# ST-Link_Stlink_v2_02.net
KiCad netlist of a schematic drawn in Altium Designer
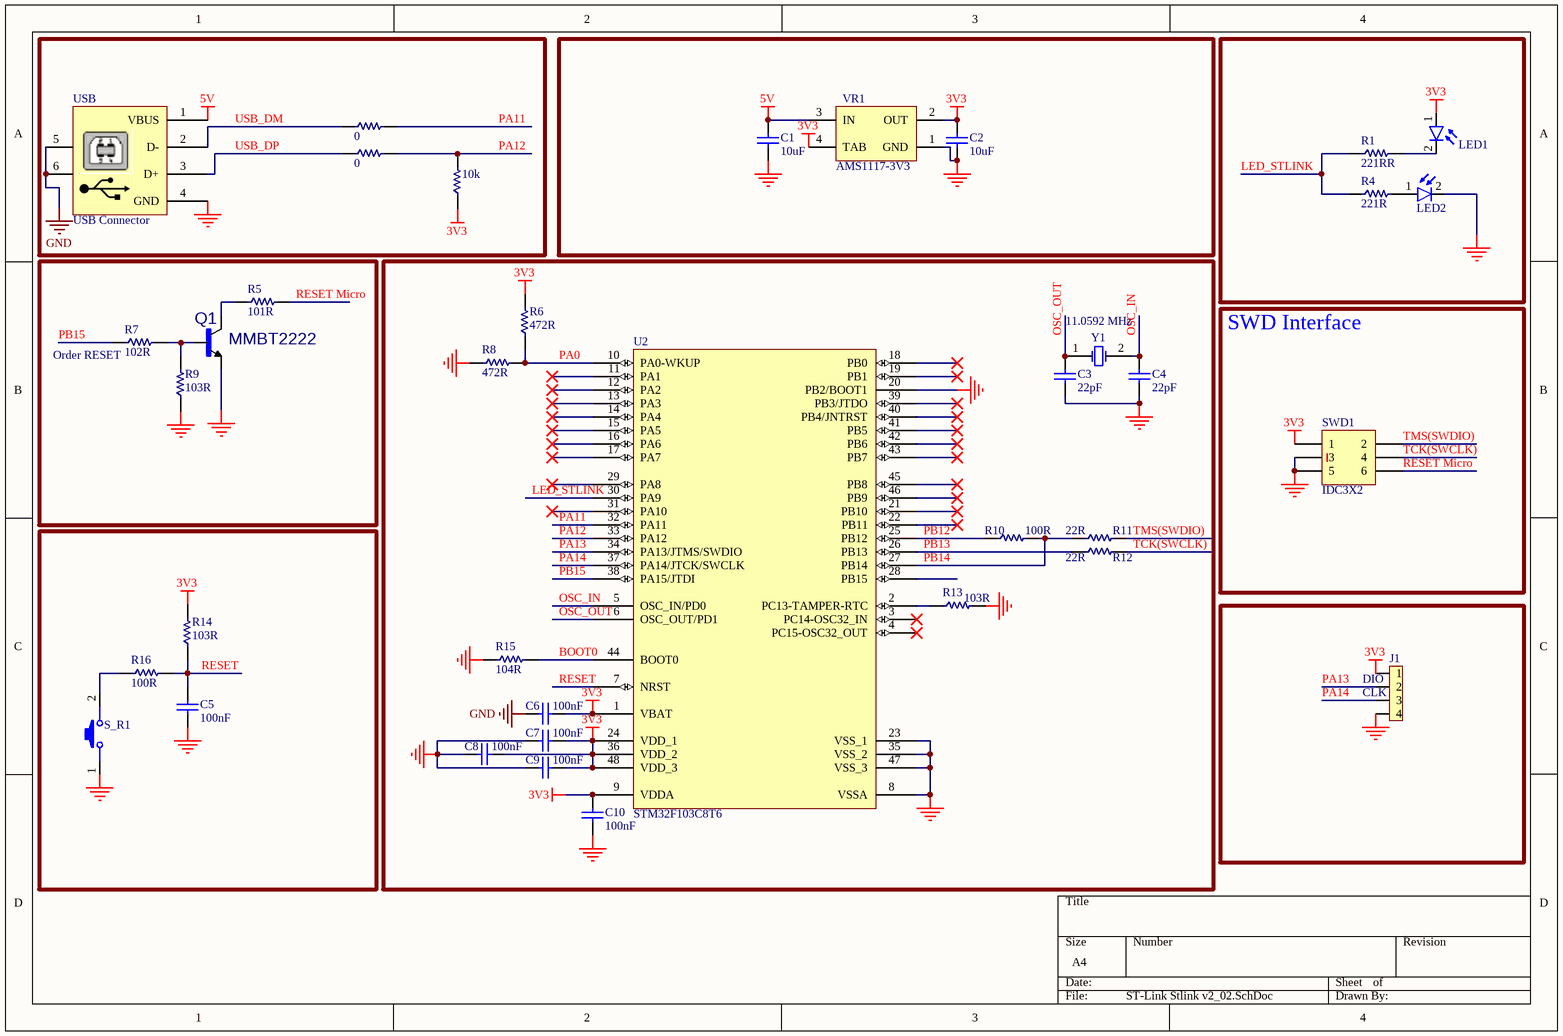
[diagram p0: ST-Link Stlink v2_02.SchDoc]

(export (version "E")
  (design (tool "Eeschema 10.0.6"))
  (components
    (comp (ref "C1")
      (value "10uF")
      (footprint "CAPC4817X12N")
      (description "CAP 1206")
      (fields (field (name "DESIGNER") "Abbas Basereh"))
      (libsource (lib "Panel Tester") (part "CAP SMD 1206"))
    )
    (comp (ref "C2")
      (value "10uF")
      (footprint "CAPC4817X12N")
      (description "CAP 1206")
      (fields (field (name "DESIGNER") "Abbas Basereh"))
      (libsource (lib "Panel Tester") (part "CAP SMD 1206"))
    )
    (comp (ref "C3")
      (value "22pF")
      (footprint "CAPC4817X12N")
      (description "CAP 1206")
      (fields (field (name "DESIGNER") "Abbas Basereh"))
      (libsource (lib "Panel Tester") (part "CAP SMD 1206"))
    )
    (comp (ref "C4")
      (value "22pF")
      (footprint "CAPC4817X12N")
      (description "CAP 1206")
      (fields (field (name "DESIGNER") "Abbas Basereh"))
      (libsource (lib "Panel Tester") (part "CAP SMD 1206"))
    )
    (comp (ref "C5")
      (value "100nF")
      (footprint "CAPC4817X12N")
      (description "CAP 1206")
      (fields (field (name "DESIGNER") "Abbas Basereh"))
      (libsource (lib "Panel Tester") (part "CAP SMD 1206"))
    )
    (comp (ref "C6")
      (value "100nF")
      (footprint "CAPC4817X12N")
      (description "CAP 1206")
      (fields (field (name "DESIGNER") "Abbas Basereh"))
      (libsource (lib "Panel Tester") (part "CAP SMD 1206"))
    )
    (comp (ref "C7")
      (value "100nF")
      (footprint "CAPC4817X12N")
      (description "CAP 1206")
      (fields (field (name "DESIGNER") "Abbas Basereh"))
      (libsource (lib "Panel Tester") (part "CAP SMD 1206"))
    )
    (comp (ref "C8")
      (value "100nF")
      (footprint "CAPC4817X12N")
      (description "CAP 1206")
      (fields (field (name "DESIGNER") "Abbas Basereh"))
      (libsource (lib "Panel Tester") (part "CAP SMD 1206"))
    )
    (comp (ref "C9")
      (value "100nF")
      (footprint "CAPC4817X12N")
      (description "CAP 1206")
      (fields (field (name "DESIGNER") "Abbas Basereh"))
      (libsource (lib "Panel Tester") (part "CAP SMD 1206"))
    )
    (comp (ref "C10")
      (value "100nF")
      (footprint "CAPC4817X12N")
      (description "CAP 1206")
      (fields (field (name "DESIGNER") "Abbas Basereh"))
      (libsource (lib "Panel Tester") (part "CAP SMD 1206"))
    )
    (comp (ref "J1")
      (value "Program Chip")
      (footprint "ZSIP04")
      (description "Connector")
      (libsource (lib "ZAltium2020SCH") (part "ZCON4"))
    )
    (comp (ref "LED1")
      (value "Color")
      (footprint "LED SMD 1206")
      (description "Infra Red Reciever Photo Diode")
      (fields (field (name "DESIGNER") "Saeid Jorablo"))
      (libsource (lib "NKH7000_Library") (part "LED"))
    )
    (comp (ref "LED2")
      (value "Color")
      (footprint "LED SMD 1206")
      (description "Infra Red Reciever Photo Diode")
      (fields (field (name "DESIGNER") "Saeid Jorablo"))
      (libsource (lib "NKH7000_Library") (part "LED"))
    )
    (comp (ref "Q1") (value "MMBT2222") (footprint "SOT23_BEC_M") (libsource (lib "OBD2") (part "MMBT2222")))
    (comp (ref "R1") (value "221RR") (footprint "RES1206") (libsource (lib "Panel Tester") (part "res")))
    (comp (ref "R2")
      (value "10k")
      (footprint "RES1206")
      (description "smd-1206-1%")
      (fields (field (name "PART") "resistor-smd-1206-10k") (field (name "DESIGNER") "rashid_behdarvand"))
      (libsource (lib "R_C_D_T") (part "resistor"))
    )
    (comp (ref "R4") (value "221R") (footprint "RES1206") (libsource (lib "Panel Tester") (part "res")))
    (comp (ref "R5") (value "101R") (footprint "RES1206") (libsource (lib "Panel Tester") (part "res")))
    (comp (ref "R6") (value "472R") (footprint "RES1206") (libsource (lib "Panel Tester") (part "res")))
    (comp (ref "R7") (value "102R") (footprint "RES1206") (libsource (lib "Panel Tester") (part "res")))
    (comp (ref "R8") (value "472R") (footprint "RES1206") (libsource (lib "Panel Tester") (part "res")))
    (comp (ref "R9") (value "103R") (footprint "RES1206") (libsource (lib "Panel Tester") (part "res")))
    (comp (ref "R10") (value "100R") (footprint "RES1206") (libsource (lib "Panel Tester") (part "res")))
    (comp (ref "R11") (value "22R") (footprint "RES1206") (libsource (lib "Panel Tester") (part "res")))
    (comp (ref "R12") (value "22R") (footprint "RES1206") (libsource (lib "Panel Tester") (part "res")))
    (comp (ref "R13") (value "103R") (footprint "RES1206") (libsource (lib "Panel Tester") (part "res")))
    (comp (ref "R14") (value "103R") (footprint "RES1206") (libsource (lib "Panel Tester") (part "res")))
    (comp (ref "R15") (value "104R") (footprint "RES1206") (libsource (lib "Panel Tester") (part "res")))
    (comp (ref "R16") (value "100R") (footprint "RES1206") (libsource (lib "Panel Tester") (part "res")))
    (comp (ref "R20")
      (value "0")
      (footprint "RES1206")
      (fields (field (name "PART") "resistor-smd-1206-0-ohm") (field (name "DESIGNER") "rashid_behdarvand"))
      (libsource (lib "R_C_D_T") (part "resistor"))
    )
    (comp (ref "R21")
      (value "0")
      (footprint "RES1206")
      (fields (field (name "PART") "resistor-smd-1206-0-ohm") (field (name "DESIGNER") "rashid_behdarvand"))
      (libsource (lib "R_C_D_T") (part "resistor"))
    )
    (comp (ref "SWD1")
      (value "IDC3X2")
      (footprint "IDC_2X3")
      (description "IDC, 6-Pin, Dual row")
      (fields (field (name "PUBLISHER") "Altium Limited"))
      (libsource (lib "Panel Tester") (part "IDC 3X2"))
    )
    (comp (ref "S_R1")
      (value "SW4")
      (footprint "SMD_ALPS_NEW")
      (description "2 Pin Push Button Switch")
      (fields (field (name "DESIGNER") "Eng. Saeid Jorablo"))
      (libsource (lib "Sensor_Simulation_Ver 03") (part "SW_PB2"))
    )
    (comp (ref "U2")
      (value "STM32F103C8T6")
      (footprint "LQFP48_M")
      (description "STM32 ARM-based 32-bit MCU with 64 Kbytes Flash, 48-pin LQFP, Industrial Temperature")
      (fields (field (name "PUBLISHER") "Altium Limited"))
      (libsource (lib "ST Microcontroller 32-Bit STM32") (part "STM32F103C8T6"))
    )
    (comp (ref "USB")
      (value "USB Connector")
      (footprint "USB2.5-2H4F")
      (description "USB Connector-B Type")
      (fields (field (name "DESIGNER") "Eng. Saeid Jorablo"))
      (libsource (lib "My Library") (part "USB"))
    )
    (comp (ref "VR1")
      (value "AMS1117-3V3")
      (footprint "MP04A_N")
      (description "x.x Volt, 800mA Low-Dropout Linear Regulator, 4-pin SOT-223")
      (fields
        (field (name "PARTNUMBER") "LM1117IMP-3.3")
        (field (name "MANUFACTURER") "National Semiconductor")
        (field (name "PUBLISHER") "Altium Limited")
      )
      (libsource (lib "My Library") (part "LM1117IMP-x.x"))
    )
    (comp (ref "Y1")
      (value "11.0592 MHz")
      (footprint "Crystal SMD")
      (description "XTAL Crystal")
      (libsource (lib "NKH7000_Library") (part "XTAL"))
    )
  )
  (nets
    (net (code "1") (name "/BOOT0") (class "Default")
      (node (ref "R15") (pin "2") (pinfunction "2_2") (pintype "passive"))
      (node (ref "U2") (pin "44") (pinfunction "BOOT0_44") (pintype "passive"))
    )
    (net (code "2") (name "/LED_STLINK") (class "Default")
      (node (ref "R1") (pin "1") (pinfunction "1_1") (pintype "passive"))
      (node (ref "R4") (pin "1") (pinfunction "1_1") (pintype "passive"))
      (node (ref "U2") (pin "30") (pinfunction "PA9_30") (pintype "bidirectional"))
    )
    (net (code "3") (name "/OSC_IN") (class "Default")
      (node (ref "C4") (pin "2") (pinfunction "2_2") (pintype "passive"))
      (node (ref "U2") (pin "5") (pinfunction "OSC_IN/PD0_5") (pintype "passive"))
      (node (ref "Y1") (pin "2") (pinfunction "OSC2_2") (pintype "passive"))
    )
    (net (code "4") (name "/OSC_OUT") (class "Default")
      (node (ref "C3") (pin "2") (pinfunction "2_2") (pintype "passive"))
      (node (ref "U2") (pin "6") (pinfunction "OSC_OUT/PD1_6") (pintype "passive"))
      (node (ref "Y1") (pin "1") (pinfunction "OSC1_1") (pintype "passive"))
    )
    (net (code "5") (name "/PA0") (class "Default")
      (node (ref "R6") (pin "1") (pinfunction "1_1") (pintype "passive"))
      (node (ref "R8") (pin "2") (pinfunction "2_2") (pintype "passive"))
      (node (ref "U2") (pin "10") (pinfunction "PA0-WKUP_10") (pintype "bidirectional"))
    )
    (net (code "6") (name "/PA11") (class "Default")
      (node (ref "R20") (pin "2") (pinfunction "2_2") (pintype "passive"))
      (node (ref "U2") (pin "32") (pinfunction "PA11_32") (pintype "bidirectional"))
    )
    (net (code "7") (name "/PA12") (class "Default")
      (node (ref "R2") (pin "2") (pinfunction "2_2") (pintype "passive"))
      (node (ref "R21") (pin "2") (pinfunction "2_2") (pintype "passive"))
      (node (ref "U2") (pin "33") (pinfunction "PA12_33") (pintype "bidirectional"))
    )
    (net (code "8") (name "/PA13") (class "Default")
      (node (ref "J1") (pin "2") (pinfunction "2_2") (pintype "passive"))
      (node (ref "U2") (pin "34") (pinfunction "PA13/JTMS/SWDIO_34") (pintype "bidirectional"))
    )
    (net (code "9") (name "/PA14") (class "Default")
      (node (ref "J1") (pin "3") (pinfunction "3_3") (pintype "passive"))
      (node (ref "U2") (pin "37") (pinfunction "PA14/JTCK/SWCLK_37") (pintype "bidirectional"))
    )
    (net (code "10") (name "/PB12") (class "Default")
      (node (ref "R10") (pin "1") (pinfunction "1_1") (pintype "passive"))
      (node (ref "U2") (pin "25") (pinfunction "PB12_25") (pintype "bidirectional"))
    )
    (net (code "11") (name "/PB13") (class "Default")
      (node (ref "R12") (pin "1") (pinfunction "1_1") (pintype "passive"))
      (node (ref "U2") (pin "26") (pinfunction "PB13_26") (pintype "bidirectional"))
    )
    (net (code "12") (name "/PB14") (class "Default")
      (node (ref "R10") (pin "2") (pinfunction "2_2") (pintype "passive"))
      (node (ref "R11") (pin "1") (pinfunction "1_1") (pintype "passive"))
      (node (ref "U2") (pin "27") (pinfunction "PB14_27") (pintype "bidirectional"))
    )
    (net (code "13") (name "/PB15") (class "Default")
      (node (ref "R7") (pin "1") (pinfunction "1_1") (pintype "passive"))
      (node (ref "U2") (pin "38") (pinfunction "PA15/JTDI_38") (pintype "bidirectional"))
    )
    (net (code "14") (name "/RESET") (class "Default")
      (node (ref "C5") (pin "2") (pinfunction "2_2") (pintype "passive"))
      (node (ref "R14") (pin "1") (pinfunction "1_1") (pintype "passive"))
      (node (ref "R16") (pin "2") (pinfunction "2_2") (pintype "passive"))
      (node (ref "U2") (pin "7") (pinfunction "NRST_7") (pintype "bidirectional"))
    )
    (net (code "15") (name "/RESET Micro") (class "Default")
      (node (ref "R5") (pin "2") (pinfunction "2_2") (pintype "passive"))
      (node (ref "SWD1") (pin "6") (pinfunction "6_6") (pintype "passive"))
    )
    (net (code "16") (name "/TCK(SWCLK)") (class "Default")
      (node (ref "R12") (pin "2") (pinfunction "2_2") (pintype "passive"))
      (node (ref "SWD1") (pin "4") (pinfunction "4_4") (pintype "passive"))
    )
    (net (code "17") (name "/TMS(SWDIO)") (class "Default")
      (node (ref "R11") (pin "2") (pinfunction "2_2") (pintype "passive"))
      (node (ref "SWD1") (pin "2") (pinfunction "2_2") (pintype "passive"))
    )
    (net (code "18") (name "/USB_DM") (class "Default")
      (node (ref "R20") (pin "1") (pinfunction "1_1") (pintype "passive"))
      (node (ref "USB") (pin "2") (pinfunction "D-_2") (pintype "passive"))
    )
    (net (code "19") (name "/USB_DP") (class "Default")
      (node (ref "R21") (pin "1") (pinfunction "1_1") (pintype "passive"))
      (node (ref "USB") (pin "3") (pinfunction "D+_3") (pintype "passive"))
    )
    (net (code "20") (name "3V3") (class "Default")
      (node (ref "C10") (pin "2") (pinfunction "2_2") (pintype "passive"))
      (node (ref "C2") (pin "2") (pinfunction "2_2") (pintype "passive"))
      (node (ref "C6") (pin "1") (pinfunction "1_1") (pintype "passive"))
      (node (ref "C7") (pin "1") (pinfunction "1_1") (pintype "passive"))
      (node (ref "C8") (pin "1") (pinfunction "1_1") (pintype "passive"))
      (node (ref "C9") (pin "1") (pinfunction "1_1") (pintype "passive"))
      (node (ref "J1") (pin "1") (pinfunction "1_1") (pintype "passive"))
      (node (ref "LED1") (pin "1") (pinfunction "A_1") (pintype "passive"))
      (node (ref "R14") (pin "2") (pinfunction "2_2") (pintype "passive"))
      (node (ref "R2") (pin "1") (pinfunction "1_1") (pintype "passive"))
      (node (ref "R6") (pin "2") (pinfunction "2_2") (pintype "passive"))
      (node (ref "SWD1") (pin "1") (pinfunction "1_1") (pintype "passive"))
      (node (ref "U2") (pin "1") (pinfunction "VBAT_1") (pintype "power_in"))
      (node (ref "U2") (pin "24") (pinfunction "VDD_1_24") (pintype "power_in"))
      (node (ref "U2") (pin "36") (pinfunction "VDD_2_36") (pintype "power_in"))
      (node (ref "U2") (pin "48") (pinfunction "VDD_3_48") (pintype "power_in"))
      (node (ref "U2") (pin "9") (pinfunction "VDDA_9") (pintype "power_in"))
      (node (ref "VR1") (pin "2") (pinfunction "OUT_2") (pintype "power_in"))
      (node (ref "VR1") (pin "4") (pinfunction "TAB_4") (pintype "power_in"))
    )
    (net (code "21") (name "5V") (class "Default")
      (node (ref "C1") (pin "2") (pinfunction "2_2") (pintype "passive"))
      (node (ref "USB") (pin "1") (pinfunction "VBUS_1") (pintype "power_in"))
      (node (ref "VR1") (pin "3") (pinfunction "IN_3") (pintype "power_in"))
    )
    (net (code "22") (name "GND") (class "Default")
      (node (ref "C1") (pin "1") (pinfunction "1_1") (pintype "passive"))
      (node (ref "C10") (pin "1") (pinfunction "1_1") (pintype "passive"))
      (node (ref "C2") (pin "1") (pinfunction "1_1") (pintype "passive"))
      (node (ref "C3") (pin "1") (pinfunction "1_1") (pintype "passive"))
      (node (ref "C4") (pin "1") (pinfunction "1_1") (pintype "passive"))
      (node (ref "C5") (pin "1") (pinfunction "1_1") (pintype "passive"))
      (node (ref "C6") (pin "2") (pinfunction "2_2") (pintype "passive"))
      (node (ref "C7") (pin "2") (pinfunction "2_2") (pintype "passive"))
      (node (ref "C8") (pin "2") (pinfunction "2_2") (pintype "passive"))
      (node (ref "C9") (pin "2") (pinfunction "2_2") (pintype "passive"))
      (node (ref "J1") (pin "4") (pinfunction "4_4") (pintype "passive"))
      (node (ref "LED2") (pin "2") (pinfunction "K_2") (pintype "passive"))
      (node (ref "Q1") (pin "2") (pinfunction "E_2") (pintype "passive"))
      (node (ref "R13") (pin "2") (pinfunction "2_2") (pintype "passive"))
      (node (ref "R15") (pin "1") (pinfunction "1_1") (pintype "passive"))
      (node (ref "R8") (pin "1") (pinfunction "1_1") (pintype "passive"))
      (node (ref "R9") (pin "1") (pinfunction "1_1") (pintype "passive"))
      (node (ref "SWD1") (pin "3") (pinfunction "3_3") (pintype "passive"))
      (node (ref "SWD1") (pin "5") (pinfunction "5_5") (pintype "passive"))
      (node (ref "S_R1") (pin "1") (pinfunction "Button_1") (pintype "passive"))
      (node (ref "U2") (pin "20") (pinfunction "PB2/BOOT1_20") (pintype "passive"))
      (node (ref "U2") (pin "23") (pinfunction "VSS_1_23") (pintype "power_in"))
      (node (ref "U2") (pin "35") (pinfunction "VSS_2_35") (pintype "power_in"))
      (node (ref "U2") (pin "47") (pinfunction "VSS_3_47") (pintype "power_in"))
      (node (ref "U2") (pin "8") (pinfunction "VSSA_8") (pintype "power_in"))
      (node (ref "USB") (pin "4") (pinfunction "GND_4") (pintype "power_in"))
      (node (ref "USB") (pin "5") (pinfunction "5_5") (pintype "passive"))
      (node (ref "USB") (pin "6") (pinfunction "6_6") (pintype "passive"))
      (node (ref "VR1") (pin "1") (pinfunction "GND_1") (pintype "power_in"))
    )
    (net (code "23") (name "Net-(LED1-K)") (class "Default")
      (node (ref "LED1") (pin "2") (pinfunction "K_2") (pintype "passive"))
      (node (ref "R1") (pin "2") (pinfunction "2_2") (pintype "passive"))
    )
    (net (code "24") (name "Net-(LED2-A)") (class "Default")
      (node (ref "LED2") (pin "1") (pinfunction "A_1") (pintype "passive"))
      (node (ref "R4") (pin "2") (pinfunction "2_2") (pintype "passive"))
    )
    (net (code "25") (name "Net-(Q1-B)") (class "Default")
      (node (ref "Q1") (pin "1") (pinfunction "B_1") (pintype "passive"))
      (node (ref "R7") (pin "2") (pinfunction "2_2") (pintype "passive"))
      (node (ref "R9") (pin "2") (pinfunction "2_2") (pintype "passive"))
    )
    (net (code "26") (name "Net-(Q1-C)") (class "Default")
      (node (ref "Q1") (pin "3") (pinfunction "C_3") (pintype "passive"))
      (node (ref "R5") (pin "1") (pinfunction "1_1") (pintype "passive"))
    )
    (net (code "27") (name "Net-(R16-Pad1)") (class "Default")
      (node (ref "R16") (pin "1") (pinfunction "1_1") (pintype "passive"))
      (node (ref "S_R1") (pin "2") (pinfunction "2_2") (pintype "passive"))
    )
    (net (code "28") (name "Net-(U2-PC13-TAMPER-RTC)") (class "Default")
      (node (ref "R13") (pin "1") (pinfunction "1_1") (pintype "passive"))
      (node (ref "U2") (pin "2") (pinfunction "PC13-TAMPER-RTC_2") (pintype "bidirectional"))
    )
    (net (code "29") (name "unconnected-(U2-PA1-Pad11)") (class "Default")
      (node (ref "U2") (pin "11") (pinfunction "PA1_11") (pintype "bidirectional+no_connect"))
    )
    (net (code "30") (name "unconnected-(U2-PA2-Pad12)") (class "Default")
      (node (ref "U2") (pin "12") (pinfunction "PA2_12") (pintype "bidirectional+no_connect"))
    )
    (net (code "31") (name "unconnected-(U2-PA3-Pad13)") (class "Default")
      (node (ref "U2") (pin "13") (pinfunction "PA3_13") (pintype "bidirectional+no_connect"))
    )
    (net (code "32") (name "unconnected-(U2-PA4-Pad14)") (class "Default")
      (node (ref "U2") (pin "14") (pinfunction "PA4_14") (pintype "bidirectional+no_connect"))
    )
    (net (code "33") (name "unconnected-(U2-PA5-Pad15)") (class "Default")
      (node (ref "U2") (pin "15") (pinfunction "PA5_15") (pintype "bidirectional+no_connect"))
    )
    (net (code "34") (name "unconnected-(U2-PA6-Pad16)") (class "Default")
      (node (ref "U2") (pin "16") (pinfunction "PA6_16") (pintype "bidirectional+no_connect"))
    )
    (net (code "35") (name "unconnected-(U2-PA7-Pad17)") (class "Default")
      (node (ref "U2") (pin "17") (pinfunction "PA7_17") (pintype "bidirectional+no_connect"))
    )
    (net (code "36") (name "unconnected-(U2-PA8-Pad29)") (class "Default")
      (node (ref "U2") (pin "29") (pinfunction "PA8_29") (pintype "bidirectional+no_connect"))
    )
    (net (code "37") (name "unconnected-(U2-PA10-Pad31)") (class "Default")
      (node (ref "U2") (pin "31") (pinfunction "PA10_31") (pintype "bidirectional+no_connect"))
    )
    (net (code "38") (name "unconnected-(U2-PB0-Pad18)") (class "Default")
      (node (ref "U2") (pin "18") (pinfunction "PB0_18") (pintype "bidirectional+no_connect"))
    )
    (net (code "39") (name "unconnected-(U2-PB1-Pad19)") (class "Default")
      (node (ref "U2") (pin "19") (pinfunction "PB1_19") (pintype "bidirectional+no_connect"))
    )
    (net (code "40") (name "unconnected-(U2-PB3{slash}JTDO-Pad39)") (class "Default")
      (node (ref "U2") (pin "39") (pinfunction "PB3/JTDO_39") (pintype "bidirectional+no_connect"))
    )
    (net (code "41") (name "unconnected-(U2-PB4{slash}JNTRST-Pad40)") (class "Default")
      (node (ref "U2") (pin "40") (pinfunction "PB4/JNTRST_40") (pintype "bidirectional+no_connect"))
    )
    (net (code "42") (name "unconnected-(U2-PB5-Pad41)") (class "Default")
      (node (ref "U2") (pin "41") (pinfunction "PB5_41") (pintype "bidirectional+no_connect"))
    )
    (net (code "43") (name "unconnected-(U2-PB6-Pad42)") (class "Default")
      (node (ref "U2") (pin "42") (pinfunction "PB6_42") (pintype "bidirectional+no_connect"))
    )
    (net (code "44") (name "unconnected-(U2-PB7-Pad43)") (class "Default")
      (node (ref "U2") (pin "43") (pinfunction "PB7_43") (pintype "bidirectional+no_connect"))
    )
    (net (code "45") (name "unconnected-(U2-PB8-Pad45)") (class "Default")
      (node (ref "U2") (pin "45") (pinfunction "PB8_45") (pintype "bidirectional+no_connect"))
    )
    (net (code "46") (name "unconnected-(U2-PB9-Pad46)") (class "Default")
      (node (ref "U2") (pin "46") (pinfunction "PB9_46") (pintype "bidirectional+no_connect"))
    )
    (net (code "47") (name "unconnected-(U2-PB10-Pad21)") (class "Default")
      (node (ref "U2") (pin "21") (pinfunction "PB10_21") (pintype "bidirectional+no_connect"))
    )
    (net (code "48") (name "unconnected-(U2-PB11-Pad22)") (class "Default")
      (node (ref "U2") (pin "22") (pinfunction "PB11_22") (pintype "bidirectional+no_connect"))
    )
    (net (code "49") (name "unconnected-(U2-PB15-Pad28)") (class "Default")
      (node (ref "U2") (pin "28") (pinfunction "PB15_28") (pintype "bidirectional"))
    )
    (net (code "50") (name "unconnected-(U2-PC14-OSC32_IN-Pad3)") (class "Default")
      (node (ref "U2") (pin "3") (pinfunction "PC14-OSC32_IN_3") (pintype "bidirectional+no_connect"))
    )
    (net (code "51") (name "unconnected-(U2-PC15-OSC32_OUT-Pad4)") (class "Default")
      (node (ref "U2") (pin "4") (pinfunction "PC15-OSC32_OUT_4") (pintype "bidirectional+no_connect"))
    )
  )
)
